# mainboard_mcu_v1_3.net
KiCad netlist of a schematic drawn in Altium Designer
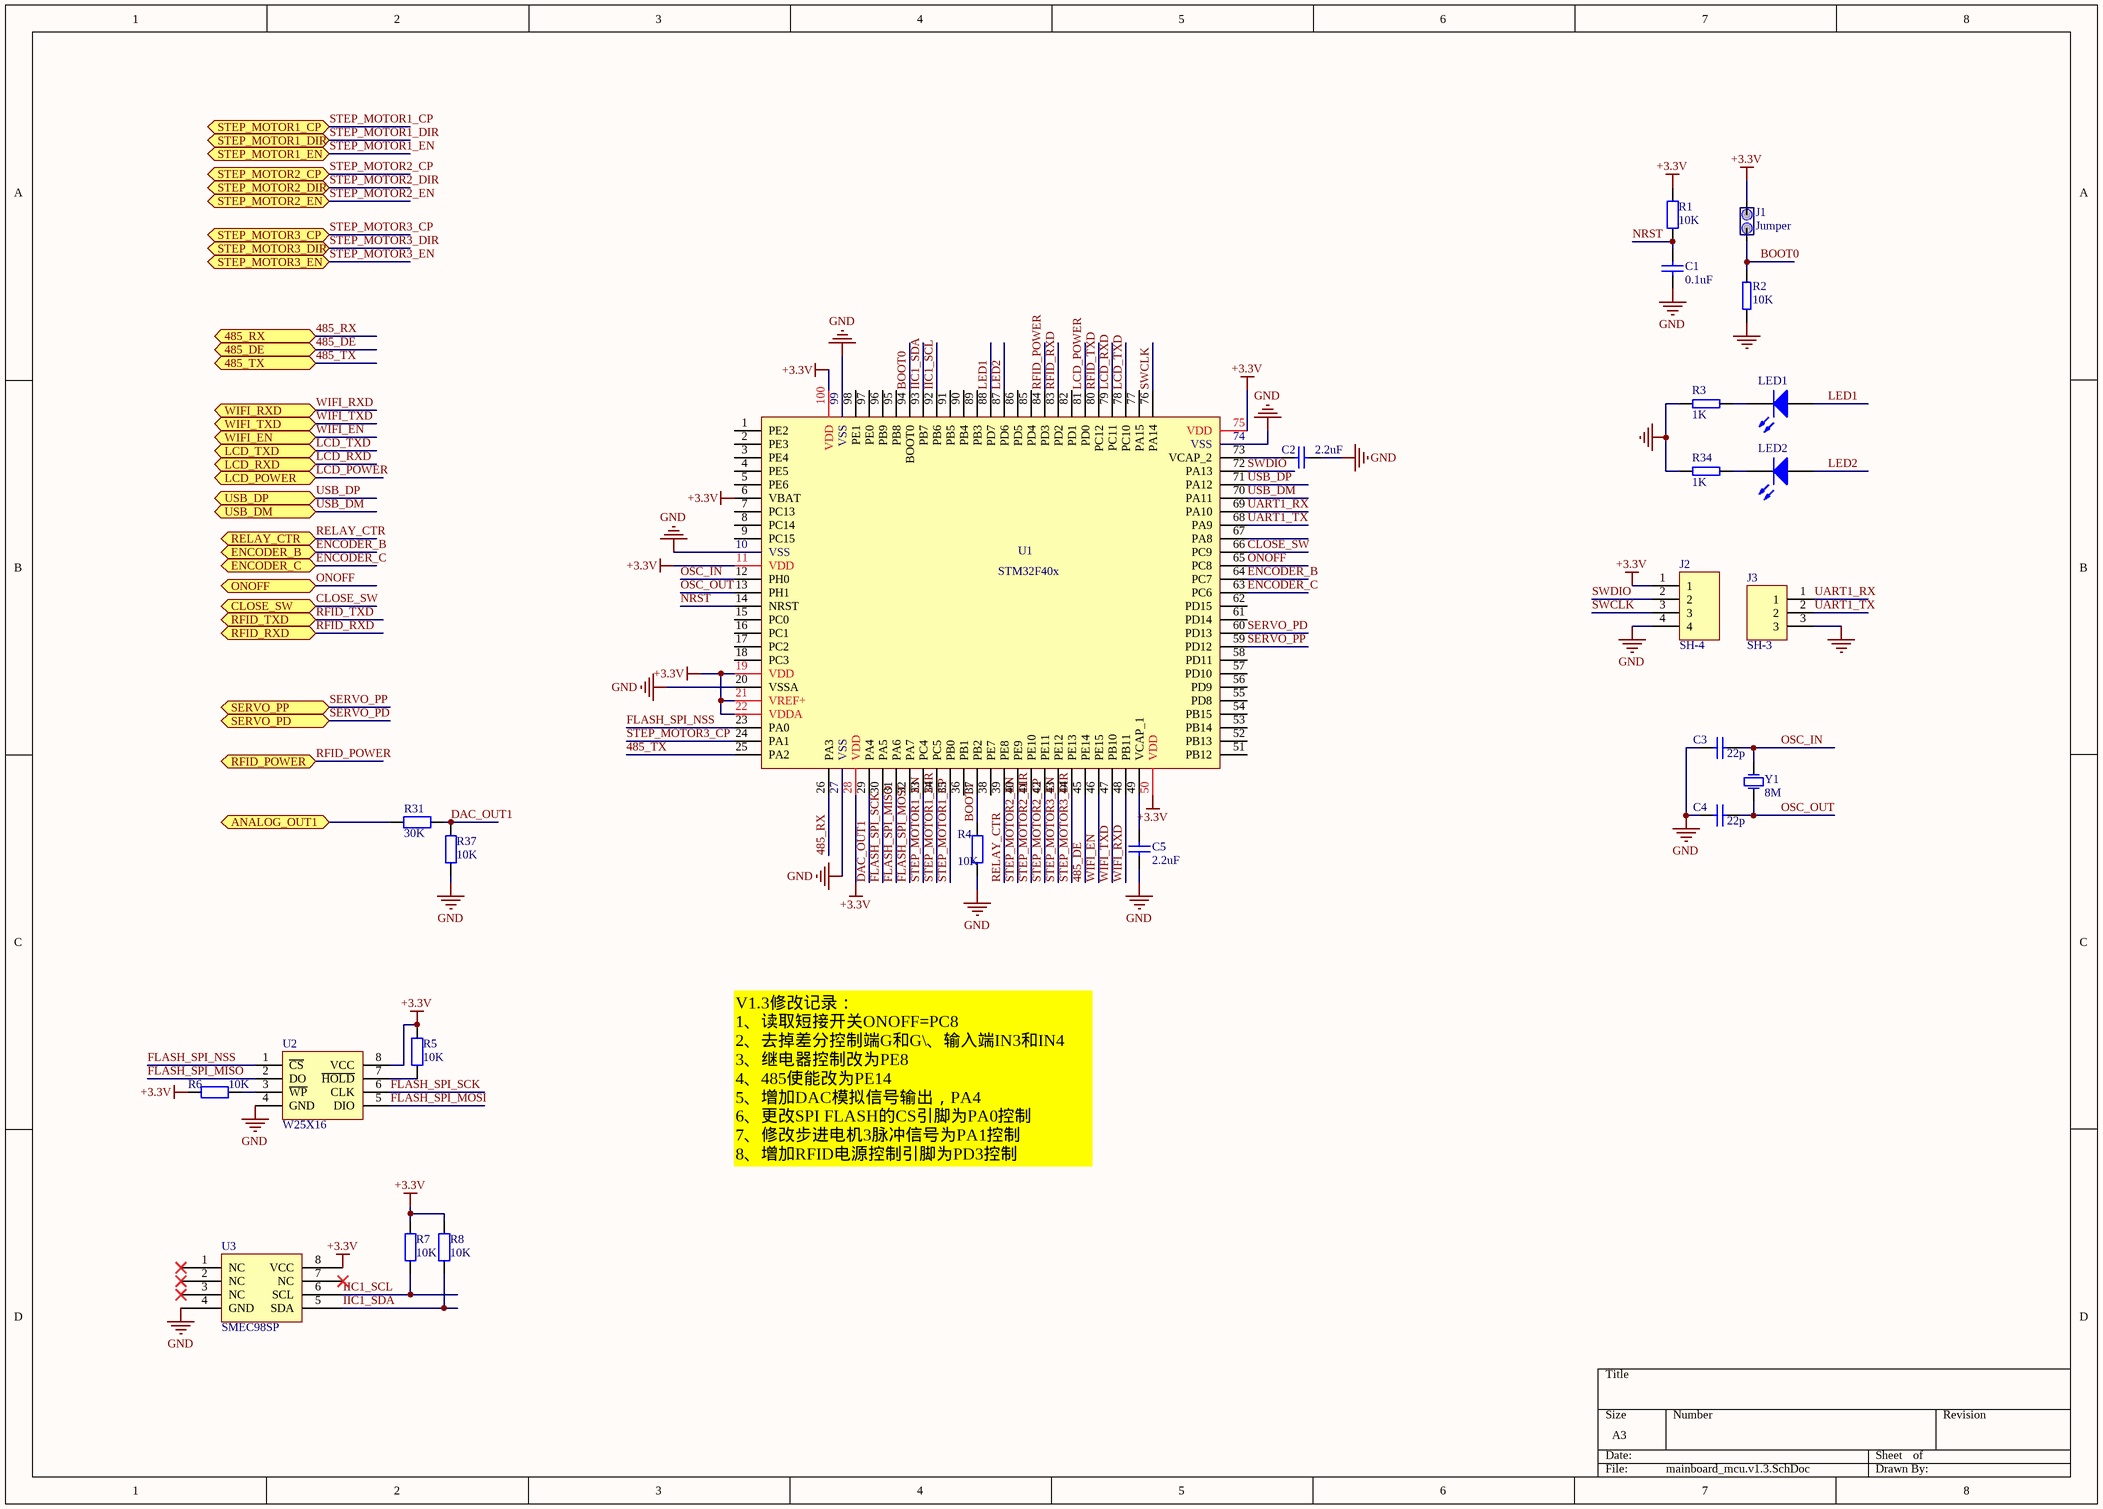
[diagram p0: mainboard_mcu.v1.3.SchDoc]

(export (version "E")
  (design (tool "Eeschema 10.0.6"))
  (components
    (comp (ref "C1")
      (value "0.1uF")
      (footprint "0805")
      (description "Capacitor")
      (fields (field (name "PUBLISHER") "Altium Limited"))
      (libsource (lib "TIAN's Schlib") (part "Cap"))
    )
    (comp (ref "C2")
      (value "2.2uF")
      (footprint "0805")
      (description "Capacitor")
      (fields (field (name "PUBLISHER") "Altium Limited"))
      (libsource (lib "TIAN's Schlib") (part "Cap"))
    )
    (comp (ref "C3")
      (value "22p")
      (footprint "0805")
      (description "Capacitor")
      (fields (field (name "PUBLISHER") "Altium Limited"))
      (libsource (lib "TIAN's Schlib") (part "Cap"))
    )
    (comp (ref "C4")
      (value "22p")
      (footprint "0805")
      (description "Capacitor")
      (fields (field (name "PUBLISHER") "Altium Limited"))
      (libsource (lib "TIAN's Schlib") (part "Cap"))
    )
    (comp (ref "C5")
      (value "2.2uF")
      (footprint "0805")
      (description "Capacitor")
      (fields (field (name "PUBLISHER") "Altium Limited"))
      (libsource (lib "TIAN's Schlib") (part "Cap"))
    )
    (comp (ref "J1") (value "Jumper") (footprint "J254-2") (libsource (lib "Connector") (part "Jumper")))
    (comp (ref "J2") (value "SH-4") (footprint "J254-4") (libsource (lib "Connector") (part "SH-4")))
    (comp (ref "J3") (value "SH-3") (footprint "J2.54-3") (libsource (lib "Connector") (part "SH-3")))
    (comp (ref "LED1")
      (value "GREEN")
      (footprint "LED")
      (description "Typical RED, GREEN, YELLOW, AMBER GaAs LED")
      (fields (field (name "PUBLISHER") "Altium Limited"))
      (libsource (lib "Miscellaneous Devices") (part "LED2"))
    )
    (comp (ref "LED2")
      (value "GREEN")
      (footprint "LED")
      (description "Typical RED, GREEN, YELLOW, AMBER GaAs LED")
      (fields (field (name "PUBLISHER") "Altium Limited"))
      (libsource (lib "Miscellaneous Devices") (part "LED2"))
    )
    (comp (ref "R1")
      (value "10K")
      (footprint "0805")
      (description "Resistor")
      (fields (field (name "PUBLISHER") "Altium Limited"))
      (libsource (lib "") (part "Res2_1"))
    )
    (comp (ref "R2")
      (value "10K")
      (footprint "0805")
      (description "电阻")
      (libsource (lib "Component") (part "RES"))
    )
    (comp (ref "R3")
      (value "1K")
      (footprint "0805")
      (description "电阻")
      (libsource (lib "Component") (part "RES"))
    )
    (comp (ref "R4")
      (value "10K")
      (footprint "0805")
      (description "Resistor")
      (fields (field (name "PUBLISHER") "Altium Limited"))
      (libsource (lib "") (part "Res2_3"))
    )
    (comp (ref "R5")
      (value "10K")
      (footprint "0805")
      (description "Resistor")
      (fields (field (name "PUBLISHER") "Altium Limited"))
      (libsource (lib "") (part "Res2_3"))
    )
    (comp (ref "R6")
      (value "10K")
      (footprint "0805")
      (description "Resistor")
      (fields (field (name "PUBLISHER") "Altium Limited"))
      (libsource (lib "") (part "Res2_2"))
    )
    (comp (ref "R7")
      (value "10K")
      (footprint "0805")
      (description "Resistor")
      (fields (field (name "PUBLISHER") "Altium Limited"))
      (libsource (lib "") (part "Res2_1"))
    )
    (comp (ref "R8")
      (value "10K")
      (footprint "0805")
      (description "Resistor")
      (fields (field (name "PUBLISHER") "Altium Limited"))
      (libsource (lib "") (part "Res2_1"))
    )
    (comp (ref "R31")
      (value "30K")
      (footprint "0805")
      (description "Resistor")
      (fields (field (name "PUBLISHER") "Altium Limited"))
      (libsource (lib "TIAN's Schlib") (part "Res2"))
    )
    (comp (ref "R34")
      (value "1K")
      (footprint "0805")
      (description "电阻")
      (libsource (lib "Component") (part "RES"))
    )
    (comp (ref "R37")
      (value "10K")
      (footprint "0805")
      (description "Resistor")
      (fields (field (name "PUBLISHER") "Altium Limited"))
      (libsource (lib "") (part "Res2_1"))
    )
    (comp (ref "U1") (value "STM32F40x") (footprint "TQFP100") (libsource (lib "Chip") (part "STM32F40x")))
    (comp (ref "U2") (value "W25X16") (footprint "SOP8") (libsource (lib "Chip") (part "W25X16")))
    (comp (ref "U3") (value "SMEC98SP") (footprint "SO-8") (libsource (lib "Chip") (part "SMEC98SP")))
    (comp (ref "Y1")
      (value "8M")
      (footprint "XTAL")
      (description "Crystal Oscillator")
      (fields (field (name "PUBLISHER") "Altium Limited"))
      (libsource (lib "TIAN's Schlib") (part "X-32.768"))
    )
  )
  (nets
    (net (code "1") (name "+3.3V") (class "Default")
      (node (ref "J1") (pin "2") (pinfunction "2_2") (pintype "passive"))
      (node (ref "J2") (pin "1") (pinfunction "1_1") (pintype "passive"))
      (node (ref "R1") (pin "2") (pinfunction "2_2") (pintype "passive"))
      (node (ref "R5") (pin "1") (pinfunction "1_1") (pintype "passive"))
      (node (ref "R6") (pin "2") (pinfunction "2_2") (pintype "passive"))
      (node (ref "R7") (pin "2") (pinfunction "2_2") (pintype "passive"))
      (node (ref "R8") (pin "2") (pinfunction "2_2") (pintype "passive"))
      (node (ref "U1") (pin "100") (pinfunction "VDD_100") (pintype "passive"))
      (node (ref "U1") (pin "11") (pinfunction "VDD_11") (pintype "passive"))
      (node (ref "U1") (pin "19") (pinfunction "VDD_19") (pintype "passive"))
      (node (ref "U1") (pin "21") (pinfunction "VREF+_21") (pintype "passive"))
      (node (ref "U1") (pin "22") (pinfunction "VDDA_22") (pintype "passive"))
      (node (ref "U1") (pin "28") (pinfunction "VDD_28") (pintype "passive"))
      (node (ref "U1") (pin "50") (pinfunction "VDD_50") (pintype "passive"))
      (node (ref "U1") (pin "6") (pinfunction "VBAT_6") (pintype "passive"))
      (node (ref "U1") (pin "75") (pinfunction "VDD_75") (pintype "passive"))
      (node (ref "U2") (pin "8") (pinfunction "VCC_8") (pintype "passive"))
      (node (ref "U3") (pin "8") (pinfunction "VCC_8") (pintype "passive"))
    )
    (net (code "2") (name "/485_DE") (class "Default")
      (node (ref "U1") (pin "45") (pinfunction "PE14_45") (pintype "passive"))
    )
    (net (code "3") (name "/485_RX") (class "Default")
      (node (ref "U1") (pin "26") (pinfunction "PA3_26") (pintype "passive"))
    )
    (net (code "4") (name "/485_TX") (class "Default")
      (node (ref "U1") (pin "25") (pinfunction "PA2_25") (pintype "passive"))
    )
    (net (code "5") (name "/ANALOG_OUT1") (class "Default")
      (node (ref "R31") (pin "1") (pinfunction "1_1") (pintype "passive"))
    )
    (net (code "6") (name "/BOOT0") (class "Default")
      (node (ref "J1") (pin "1") (pinfunction "1_1") (pintype "passive"))
      (node (ref "R2") (pin "1") (pinfunction "1_1") (pintype "passive"))
      (node (ref "U1") (pin "94") (pinfunction "BOOT0_94") (pintype "passive"))
    )
    (net (code "7") (name "/BOOT1") (class "Default")
      (node (ref "R4") (pin "1") (pinfunction "1_1") (pintype "passive"))
      (node (ref "U1") (pin "37") (pinfunction "PB2_37") (pintype "passive"))
    )
    (net (code "8") (name "/CLOSE_SW") (class "Default")
      (node (ref "U1") (pin "66") (pinfunction "PC9_66") (pintype "passive"))
    )
    (net (code "9") (name "/DAC_OUT1") (class "Default")
      (node (ref "R31") (pin "2") (pinfunction "2_2") (pintype "passive"))
      (node (ref "R37") (pin "2") (pinfunction "2_2") (pintype "passive"))
      (node (ref "U1") (pin "29") (pinfunction "PA4_29") (pintype "passive"))
    )
    (net (code "10") (name "/ENCODER_B") (class "Default")
      (node (ref "U1") (pin "64") (pinfunction "PC7_64") (pintype "passive"))
    )
    (net (code "11") (name "/ENCODER_C") (class "Default")
      (node (ref "U1") (pin "63") (pinfunction "PC6_63") (pintype "passive"))
    )
    (net (code "12") (name "/FLASH_SPI_MISO") (class "Default")
      (node (ref "U1") (pin "31") (pinfunction "PA6_31") (pintype "passive"))
      (node (ref "U2") (pin "2") (pinfunction "DO_2") (pintype "passive"))
    )
    (net (code "13") (name "/FLASH_SPI_MOSI") (class "Default")
      (node (ref "U1") (pin "32") (pinfunction "PA7_32") (pintype "passive"))
      (node (ref "U2") (pin "5") (pinfunction "DIO_5") (pintype "passive"))
    )
    (net (code "14") (name "/FLASH_SPI_NSS") (class "Default")
      (node (ref "U1") (pin "23") (pinfunction "PA0_23") (pintype "passive"))
      (node (ref "U2") (pin "1") (pinfunction "~{CS}_1") (pintype "passive"))
    )
    (net (code "15") (name "/FLASH_SPI_SCK") (class "Default")
      (node (ref "U1") (pin "30") (pinfunction "PA5_30") (pintype "passive"))
      (node (ref "U2") (pin "6") (pinfunction "CLK_6") (pintype "passive"))
    )
    (net (code "16") (name "/IIC1_SCL") (class "Default")
      (node (ref "R7") (pin "1") (pinfunction "1_1") (pintype "passive"))
      (node (ref "U1") (pin "92") (pinfunction "PB6_92") (pintype "passive"))
      (node (ref "U3") (pin "6") (pinfunction "SCL_6") (pintype "passive"))
    )
    (net (code "17") (name "/IIC1_SDA") (class "Default")
      (node (ref "R8") (pin "1") (pinfunction "1_1") (pintype "passive"))
      (node (ref "U1") (pin "93") (pinfunction "PB7_93") (pintype "passive"))
      (node (ref "U3") (pin "5") (pinfunction "SDA_5") (pintype "passive"))
    )
    (net (code "18") (name "/LCD_POWER") (class "Default")
      (node (ref "U1") (pin "81") (pinfunction "PD0_81") (pintype "passive"))
    )
    (net (code "19") (name "/LCD_RXD") (class "Default")
      (node (ref "U1") (pin "79") (pinfunction "PC11_79") (pintype "passive"))
    )
    (net (code "20") (name "/LCD_TXD") (class "Default")
      (node (ref "U1") (pin "78") (pinfunction "PC10_78") (pintype "passive"))
    )
    (net (code "21") (name "/LED1") (class "Default")
      (node (ref "LED1") (pin "1") (pinfunction "A_1") (pintype "passive"))
      (node (ref "U1") (pin "88") (pinfunction "PD7_88") (pintype "passive"))
    )
    (net (code "22") (name "/LED2") (class "Default")
      (node (ref "LED2") (pin "1") (pinfunction "A_1") (pintype "passive"))
      (node (ref "U1") (pin "87") (pinfunction "PD6_87") (pintype "passive"))
    )
    (net (code "23") (name "/NRST") (class "Default")
      (node (ref "C1") (pin "2") (pinfunction "2_2") (pintype "passive"))
      (node (ref "R1") (pin "1") (pinfunction "1_1") (pintype "passive"))
      (node (ref "U1") (pin "14") (pinfunction "NRST_14") (pintype "passive"))
    )
    (net (code "24") (name "/ONOFF") (class "Default")
      (node (ref "U1") (pin "65") (pinfunction "PC8_65") (pintype "passive"))
    )
    (net (code "25") (name "/OSC_IN") (class "Default")
      (node (ref "C3") (pin "1") (pinfunction "1_1") (pintype "passive"))
      (node (ref "U1") (pin "12") (pinfunction "PH0_12") (pintype "passive"))
      (node (ref "Y1") (pin "2") (pinfunction "OSC2_2") (pintype "passive"))
    )
    (net (code "26") (name "/OSC_OUT") (class "Default")
      (node (ref "C4") (pin "1") (pinfunction "1_1") (pintype "passive"))
      (node (ref "U1") (pin "13") (pinfunction "PH1_13") (pintype "passive"))
      (node (ref "Y1") (pin "1") (pinfunction "OSC1_1") (pintype "passive"))
    )
    (net (code "27") (name "/RELAY_CTR") (class "Default")
      (node (ref "U1") (pin "39") (pinfunction "PE8_39") (pintype "passive"))
    )
    (net (code "28") (name "/RFID_POWER") (class "Default")
      (node (ref "U1") (pin "84") (pinfunction "PD3_84") (pintype "passive"))
    )
    (net (code "29") (name "/RFID_RXD") (class "Default")
      (node (ref "U1") (pin "83") (pinfunction "PD2_83") (pintype "passive"))
    )
    (net (code "30") (name "/RFID_TXD") (class "Default")
      (node (ref "U1") (pin "80") (pinfunction "PC12_80") (pintype "passive"))
    )
    (net (code "31") (name "/SERVO_PD") (class "Default")
      (node (ref "U1") (pin "60") (pinfunction "PD13_60") (pintype "passive"))
    )
    (net (code "32") (name "/SERVO_PP") (class "Default")
      (node (ref "U1") (pin "59") (pinfunction "PD12_59") (pintype "passive"))
    )
    (net (code "33") (name "/STEP_MOTOR1_CP") (class "Default")
      (node (ref "U1") (pin "35") (pinfunction "PB0_35") (pintype "passive"))
    )
    (net (code "34") (name "/STEP_MOTOR1_DIR") (class "Default")
      (node (ref "U1") (pin "34") (pinfunction "PC5_34") (pintype "passive"))
    )
    (net (code "35") (name "/STEP_MOTOR1_EN") (class "Default")
      (node (ref "U1") (pin "33") (pinfunction "PC4_33") (pintype "passive"))
    )
    (net (code "36") (name "/STEP_MOTOR2_CP") (class "Default")
      (node (ref "U1") (pin "42") (pinfunction "PE11_42") (pintype "passive"))
    )
    (net (code "37") (name "/STEP_MOTOR2_DIR") (class "Default")
      (node (ref "U1") (pin "41") (pinfunction "PE10_41") (pintype "passive"))
    )
    (net (code "38") (name "/STEP_MOTOR2_EN") (class "Default")
      (node (ref "U1") (pin "40") (pinfunction "PE9_40") (pintype "passive"))
    )
    (net (code "39") (name "/STEP_MOTOR3_CP") (class "Default")
      (node (ref "U1") (pin "24") (pinfunction "PA1_24") (pintype "passive"))
    )
    (net (code "40") (name "/STEP_MOTOR3_DIR") (class "Default")
      (node (ref "U1") (pin "44") (pinfunction "PE13_44") (pintype "passive"))
    )
    (net (code "41") (name "/STEP_MOTOR3_EN") (class "Default")
      (node (ref "U1") (pin "43") (pinfunction "PE12_43") (pintype "passive"))
    )
    (net (code "42") (name "/SWCLK") (class "Default")
      (node (ref "J2") (pin "3") (pinfunction "3_3") (pintype "passive"))
      (node (ref "U1") (pin "76") (pinfunction "PA14_76") (pintype "passive"))
    )
    (net (code "43") (name "/SWDIO") (class "Default")
      (node (ref "J2") (pin "2") (pinfunction "2_2") (pintype "passive"))
      (node (ref "U1") (pin "72") (pinfunction "PA13_72") (pintype "passive"))
    )
    (net (code "44") (name "/UART1_RX") (class "Default")
      (node (ref "J3") (pin "1") (pinfunction "1_1") (pintype "passive"))
      (node (ref "U1") (pin "69") (pinfunction "PA10_69") (pintype "passive"))
    )
    (net (code "45") (name "/UART1_TX") (class "Default")
      (node (ref "J3") (pin "2") (pinfunction "2_2") (pintype "passive"))
      (node (ref "U1") (pin "68") (pinfunction "PA9_68") (pintype "passive"))
    )
    (net (code "46") (name "/USB_DM") (class "Default")
      (node (ref "U1") (pin "70") (pinfunction "PA11_70") (pintype "passive"))
    )
    (net (code "47") (name "/USB_DP") (class "Default")
      (node (ref "U1") (pin "71") (pinfunction "PA12_71") (pintype "passive"))
    )
    (net (code "48") (name "/WIFI_EN") (class "Default")
      (node (ref "U1") (pin "46") (pinfunction "PE15_46") (pintype "passive"))
    )
    (net (code "49") (name "/WIFI_RXD") (class "Default")
      (node (ref "U1") (pin "48") (pinfunction "PB11_48") (pintype "passive"))
    )
    (net (code "50") (name "/WIFI_TXD") (class "Default")
      (node (ref "U1") (pin "47") (pinfunction "PB10_47") (pintype "passive"))
    )
    (net (code "51") (name "GND") (class "Default")
      (node (ref "C1") (pin "1") (pinfunction "1_1") (pintype "passive"))
      (node (ref "C2") (pin "1") (pinfunction "1_1") (pintype "passive"))
      (node (ref "C3") (pin "2") (pinfunction "2_2") (pintype "passive"))
      (node (ref "C4") (pin "2") (pinfunction "2_2") (pintype "passive"))
      (node (ref "C5") (pin "2") (pinfunction "2_2") (pintype "passive"))
      (node (ref "J2") (pin "4") (pinfunction "4_4") (pintype "passive"))
      (node (ref "J3") (pin "3") (pinfunction "3_3") (pintype "passive"))
      (node (ref "R2") (pin "2") (pinfunction "2_2") (pintype "passive"))
      (node (ref "R3") (pin "2") (pinfunction "2_2") (pintype "passive"))
      (node (ref "R34") (pin "2") (pinfunction "2_2") (pintype "passive"))
      (node (ref "R37") (pin "1") (pinfunction "1_1") (pintype "passive"))
      (node (ref "R4") (pin "2") (pinfunction "2_2") (pintype "passive"))
      (node (ref "U1") (pin "10") (pinfunction "VSS_10") (pintype "passive"))
      (node (ref "U1") (pin "20") (pinfunction "VSSA_20") (pintype "passive"))
      (node (ref "U1") (pin "27") (pinfunction "VSS_27") (pintype "passive"))
      (node (ref "U1") (pin "74") (pinfunction "VSS_74") (pintype "passive"))
      (node (ref "U1") (pin "99") (pinfunction "VSS_99") (pintype "passive"))
      (node (ref "U2") (pin "4") (pinfunction "GND_4") (pintype "passive"))
      (node (ref "U3") (pin "4") (pinfunction "GND_4") (pintype "passive"))
    )
    (net (code "52") (name "Net-(LED1-K)") (class "Default")
      (node (ref "LED1") (pin "2") (pinfunction "K_2") (pintype "passive"))
      (node (ref "R3") (pin "1") (pinfunction "1_1") (pintype "passive"))
    )
    (net (code "53") (name "Net-(LED2-K)") (class "Default")
      (node (ref "LED2") (pin "2") (pinfunction "K_2") (pintype "passive"))
      (node (ref "R34") (pin "1") (pinfunction "1_1") (pintype "passive"))
    )
    (net (code "54") (name "Net-(U1-VCAP_1)") (class "Default")
      (node (ref "C5") (pin "1") (pinfunction "1_1") (pintype "passive"))
      (node (ref "U1") (pin "49") (pinfunction "VCAP_1_49") (pintype "passive"))
    )
    (net (code "55") (name "Net-(U1-VCAP_2)") (class "Default")
      (node (ref "C2") (pin "2") (pinfunction "2_2") (pintype "passive"))
      (node (ref "U1") (pin "73") (pinfunction "VCAP_2_73") (pintype "passive"))
    )
    (net (code "56") (name "Net-(U2-~{HOLD})") (class "Default")
      (node (ref "R5") (pin "2") (pinfunction "2_2") (pintype "passive"))
      (node (ref "U2") (pin "7") (pinfunction "~{HOLD}_7") (pintype "passive"))
    )
    (net (code "57") (name "Net-(U2-~{WP})") (class "Default")
      (node (ref "R6") (pin "1") (pinfunction "1_1") (pintype "passive"))
      (node (ref "U2") (pin "3") (pinfunction "~{WP}_3") (pintype "passive"))
    )
    (net (code "58") (name "unconnected-(U1-PA8-Pad67)") (class "Default")
      (node (ref "U1") (pin "67") (pinfunction "PA8_67") (pintype "passive"))
    )
    (net (code "59") (name "unconnected-(U1-PA15-Pad77)") (class "Default")
      (node (ref "U1") (pin "77") (pinfunction "PA15_77") (pintype "passive"))
    )
    (net (code "60") (name "unconnected-(U1-PB1-Pad36)") (class "Default")
      (node (ref "U1") (pin "36") (pinfunction "PB1_36") (pintype "passive"))
    )
    (net (code "61") (name "unconnected-(U1-PB3-Pad89)") (class "Default")
      (node (ref "U1") (pin "89") (pinfunction "PB3_89") (pintype "passive"))
    )
    (net (code "62") (name "unconnected-(U1-PB4-Pad90)") (class "Default")
      (node (ref "U1") (pin "90") (pinfunction "PB4_90") (pintype "passive"))
    )
    (net (code "63") (name "unconnected-(U1-PB5-Pad91)") (class "Default")
      (node (ref "U1") (pin "91") (pinfunction "PB5_91") (pintype "passive"))
    )
    (net (code "64") (name "unconnected-(U1-PB8-Pad95)") (class "Default")
      (node (ref "U1") (pin "95") (pinfunction "PB8_95") (pintype "passive"))
    )
    (net (code "65") (name "unconnected-(U1-PB9-Pad96)") (class "Default")
      (node (ref "U1") (pin "96") (pinfunction "PB9_96") (pintype "passive"))
    )
    (net (code "66") (name "unconnected-(U1-PB12-Pad51)") (class "Default")
      (node (ref "U1") (pin "51") (pinfunction "PB12_51") (pintype "passive"))
    )
    (net (code "67") (name "unconnected-(U1-PB13-Pad52)") (class "Default")
      (node (ref "U1") (pin "52") (pinfunction "PB13_52") (pintype "passive"))
    )
    (net (code "68") (name "unconnected-(U1-PB14-Pad53)") (class "Default")
      (node (ref "U1") (pin "53") (pinfunction "PB14_53") (pintype "passive"))
    )
    (net (code "69") (name "unconnected-(U1-PB15-Pad54)") (class "Default")
      (node (ref "U1") (pin "54") (pinfunction "PB15_54") (pintype "passive"))
    )
    (net (code "70") (name "unconnected-(U1-PC0-Pad15)") (class "Default")
      (node (ref "U1") (pin "15") (pinfunction "PC0_15") (pintype "passive"))
    )
    (net (code "71") (name "unconnected-(U1-PC1-Pad16)") (class "Default")
      (node (ref "U1") (pin "16") (pinfunction "PC1_16") (pintype "passive"))
    )
    (net (code "72") (name "unconnected-(U1-PC2-Pad17)") (class "Default")
      (node (ref "U1") (pin "17") (pinfunction "PC2_17") (pintype "passive"))
    )
    (net (code "73") (name "unconnected-(U1-PC3-Pad18)") (class "Default")
      (node (ref "U1") (pin "18") (pinfunction "PC3_18") (pintype "passive"))
    )
    (net (code "74") (name "unconnected-(U1-PC13-Pad7)") (class "Default")
      (node (ref "U1") (pin "7") (pinfunction "PC13_7") (pintype "passive"))
    )
    (net (code "75") (name "unconnected-(U1-PC14-Pad8)") (class "Default")
      (node (ref "U1") (pin "8") (pinfunction "PC14_8") (pintype "passive"))
    )
    (net (code "76") (name "unconnected-(U1-PC15-Pad9)") (class "Default")
      (node (ref "U1") (pin "9") (pinfunction "PC15_9") (pintype "passive"))
    )
    (net (code "77") (name "unconnected-(U1-PD1-Pad82)") (class "Default")
      (node (ref "U1") (pin "82") (pinfunction "PD1_82") (pintype "passive"))
    )
    (net (code "78") (name "unconnected-(U1-PD4-Pad85)") (class "Default")
      (node (ref "U1") (pin "85") (pinfunction "PD4_85") (pintype "passive"))
    )
    (net (code "79") (name "unconnected-(U1-PD5-Pad86)") (class "Default")
      (node (ref "U1") (pin "86") (pinfunction "PD5_86") (pintype "passive"))
    )
    (net (code "80") (name "unconnected-(U1-PD8-Pad55)") (class "Default")
      (node (ref "U1") (pin "55") (pinfunction "PD8_55") (pintype "passive"))
    )
    (net (code "81") (name "unconnected-(U1-PD9-Pad56)") (class "Default")
      (node (ref "U1") (pin "56") (pinfunction "PD9_56") (pintype "passive"))
    )
    (net (code "82") (name "unconnected-(U1-PD10-Pad57)") (class "Default")
      (node (ref "U1") (pin "57") (pinfunction "PD10_57") (pintype "passive"))
    )
    (net (code "83") (name "unconnected-(U1-PD11-Pad58)") (class "Default")
      (node (ref "U1") (pin "58") (pinfunction "PD11_58") (pintype "passive"))
    )
    (net (code "84") (name "unconnected-(U1-PD14-Pad61)") (class "Default")
      (node (ref "U1") (pin "61") (pinfunction "PD14_61") (pintype "passive"))
    )
    (net (code "85") (name "unconnected-(U1-PD15-Pad62)") (class "Default")
      (node (ref "U1") (pin "62") (pinfunction "PD15_62") (pintype "passive"))
    )
    (net (code "86") (name "unconnected-(U1-PE0-Pad97)") (class "Default")
      (node (ref "U1") (pin "97") (pinfunction "PE0_97") (pintype "passive"))
    )
    (net (code "87") (name "unconnected-(U1-PE1-Pad98)") (class "Default")
      (node (ref "U1") (pin "98") (pinfunction "PE1_98") (pintype "passive"))
    )
    (net (code "88") (name "unconnected-(U1-PE2-Pad1)") (class "Default")
      (node (ref "U1") (pin "1") (pinfunction "PE2_1") (pintype "passive"))
    )
    (net (code "89") (name "unconnected-(U1-PE3-Pad2)") (class "Default")
      (node (ref "U1") (pin "2") (pinfunction "PE3_2") (pintype "passive"))
    )
    (net (code "90") (name "unconnected-(U1-PE4-Pad3)") (class "Default")
      (node (ref "U1") (pin "3") (pinfunction "PE4_3") (pintype "passive"))
    )
    (net (code "91") (name "unconnected-(U1-PE5-Pad4)") (class "Default")
      (node (ref "U1") (pin "4") (pinfunction "PE5_4") (pintype "passive"))
    )
    (net (code "92") (name "unconnected-(U1-PE6-Pad5)") (class "Default")
      (node (ref "U1") (pin "5") (pinfunction "PE6_5") (pintype "passive"))
    )
    (net (code "93") (name "unconnected-(U1-PE7-Pad38)") (class "Default")
      (node (ref "U1") (pin "38") (pinfunction "PE7_38") (pintype "passive"))
    )
    (net (code "94") (name "unconnected-(U3-NC-Pad1)") (class "Default")
      (node (ref "U3") (pin "1") (pinfunction "NC_1") (pintype "passive+no_connect"))
    )
    (net (code "95") (name "unconnected-(U3-NC-Pad2)") (class "Default")
      (node (ref "U3") (pin "2") (pinfunction "NC_2") (pintype "passive+no_connect"))
    )
    (net (code "96") (name "unconnected-(U3-NC-Pad3)") (class "Default")
      (node (ref "U3") (pin "3") (pinfunction "NC_3") (pintype "passive+no_connect"))
    )
    (net (code "97") (name "unconnected-(U3-NC-Pad7)") (class "Default")
      (node (ref "U3") (pin "7") (pinfunction "NC_7") (pintype "passive+no_connect"))
    )
  )
)
